# Power_Regulators_Ether2V5.net
KiCad netlist of a schematic drawn in Altium Designer
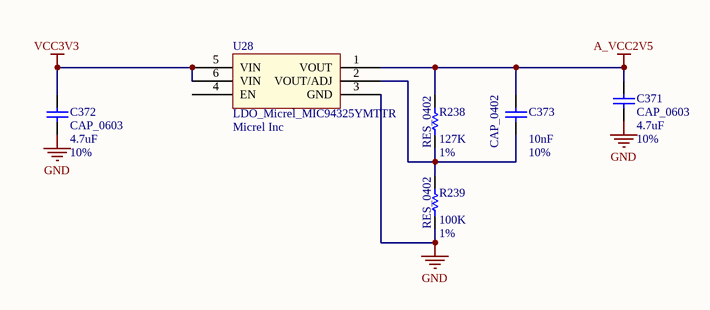
[diagram p0: Power_Regulators_Ether2V5.SchDoc]

(export (version "E")
  (design (tool "Eeschema 10.0.6"))
  (components
    (comp (ref "C371")
      (value "CAP_0603")
      (footprint "CAPC0603(1608)100_N")
      (description "4.7uF, ceramic, 10%, 10V X5R, 0603")
      (fields
        (field (name "ALTIUM_VALUE") "4.7uF")
        (field (name "TOLERANCE") "10%")
        (field (name "PART NUMBER") "LMK107BJ475KA-T")
        (field (name "MANUFACTURER") "Taiyo Yuden")
      )
      (libsource (lib "COMRAD_Database") (part "CAP_0603"))
    )
    (comp (ref "C372")
      (value "CAP_0603")
      (footprint "CAPC0603(1608)100_N")
      (description "4.7uF, ceramic, 10%, 10V X5R, 0603")
      (fields
        (field (name "ALTIUM_VALUE") "4.7uF")
        (field (name "TOLERANCE") "10%")
        (field (name "PART NUMBER") "LMK107BJ475KA-T")
        (field (name "MANUFACTURER") "Taiyo Yuden")
      )
      (libsource (lib "COMRAD_Database") (part "CAP_0603"))
    )
    (comp (ref "C373")
      (value "CAP_0402")
      (footprint "CAPC0402(1005)60_N")
      (description "10000pF, ceramic, 10% 6.3V X5R, 0402")
      (fields
        (field (name "ALTIUM_VALUE") "10nF")
        (field (name "TOLERANCE") "10%")
        (field (name "PART NUMBER") "GRM155R60J103KA01D")
        (field (name "MANUFACTURER") "Murata Electronics North America")
      )
      (libsource (lib "COMRAD_Database") (part "CAP_0402"))
    )
    (comp (ref "R238")
      (value "RES_0402")
      (footprint "RESC0402(1005)_N")
      (description "127K ohm, 1%, 1/16W, 0402")
      (fields
        (field (name "ALTIUM_VALUE") "127K")
        (field (name "TOLERANCE") "1%")
        (field (name "PART NUMBER") "MCR01MZPF1273")
        (field (name "MANUFACTURER") "ROHM")
      )
      (libsource (lib "COMRAD_Database") (part "RES_0402"))
    )
    (comp (ref "R239")
      (value "RES_0402")
      (footprint "RESC0402(1005)_N")
      (description "100K ohm, 1%, 1/16W, 0402")
      (fields
        (field (name "ALTIUM_VALUE") "100K")
        (field (name "TOLERANCE") "1%")
        (field (name "PART NUMBER") "MCR01MZPF1003")
        (field (name "MANUFACTURER") "ROHM")
      )
      (libsource (lib "COMRAD_Database") (part "RES_0402"))
    )
    (comp (ref "U28")
      (value "LDO_Micrel_MIC94325YMTTR")
      (footprint "LDO_Micrel_MIC94325YMTTR_TDFN-6")
      (description "IC REG LDO ADJ .5A 6TDFN")
      (fields (field (name "PART NUMBER") "MIC94325YMTTR") (field (name "MANUFACTURER") "Micrel Inc"))
      (libsource (lib "COMRAD_Database") (part "LDO_Micrel_MIC94325YMTTR"))
    )
  )
  (nets
    (net (code "1") (name "A_VCC2V5") (class "Default")
      (node (ref "C371") (pin "2") (pinfunction "2_2") (pintype "passive"))
      (node (ref "C373") (pin "2") (pinfunction "2_2") (pintype "passive"))
      (node (ref "R238") (pin "2") (pinfunction "2_2") (pintype "passive"))
      (node (ref "U28") (pin "1") (pinfunction "VOUT_1") (pintype "passive"))
    )
    (net (code "2") (name "GND") (class "Default")
      (node (ref "C371") (pin "1") (pinfunction "1_1") (pintype "passive"))
      (node (ref "C372") (pin "1") (pinfunction "1_1") (pintype "passive"))
      (node (ref "R239") (pin "1") (pinfunction "1_1") (pintype "passive"))
      (node (ref "U28") (pin "3") (pinfunction "GND_3") (pintype "passive"))
    )
    (net (code "3") (name "Net-(U28-VOUT{slash}ADJ)") (class "Default")
      (node (ref "C373") (pin "1") (pinfunction "1_1") (pintype "passive"))
      (node (ref "R238") (pin "1") (pinfunction "1_1") (pintype "passive"))
      (node (ref "R239") (pin "2") (pinfunction "2_2") (pintype "passive"))
      (node (ref "U28") (pin "2") (pinfunction "VOUT/ADJ_2") (pintype "passive"))
    )
    (net (code "4") (name "VCC3V3") (class "Default")
      (node (ref "C372") (pin "2") (pinfunction "2_2") (pintype "passive"))
      (node (ref "U28") (pin "5") (pinfunction "VIN_5") (pintype "passive"))
      (node (ref "U28") (pin "6") (pinfunction "VIN_6") (pintype "passive"))
    )
    (net (code "5") (name "unconnected-(U28-EN-Pad4)") (class "Default")
      (node (ref "U28") (pin "4") (pinfunction "EN_4") (pintype "passive"))
    )
  )
)
